# Sensor_Cameralink.net
KiCad netlist of a schematic drawn in EAGLE
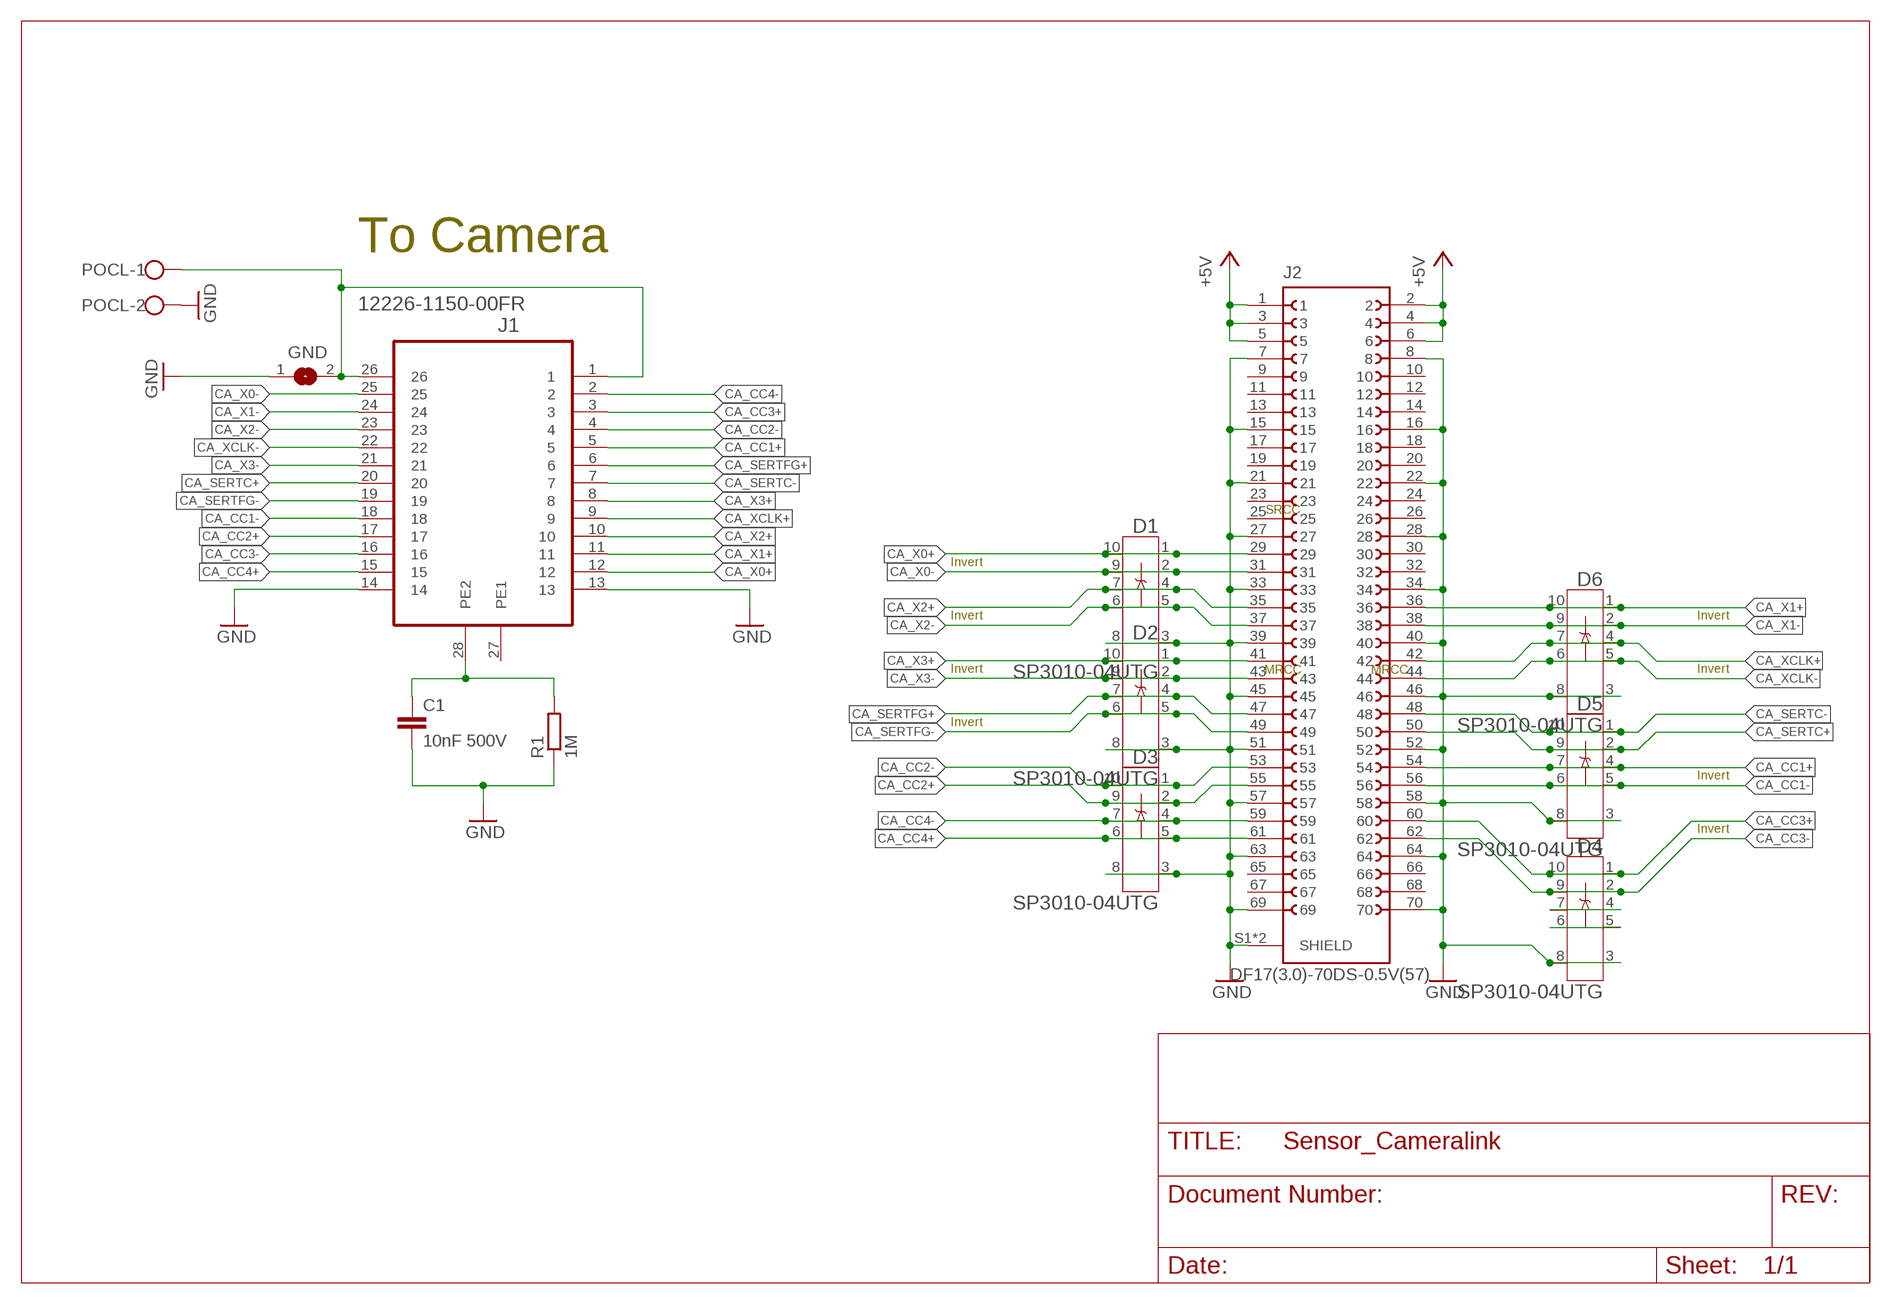
[diagram p0: schematic, sheet 1]

(export (version "E")
  (design (tool "Eeschema 10.0.6"))
  (components
    (comp (ref "C1")
      (value "10nF 500V")
      (footprint "eagle-import:C0805")
      (libsource (lib "eagle-import") (part "C-EUC0805"))
    )
    (comp (ref "D1")
      (value "SP3010-04UTG")
      (footprint "eagle-import:UDFEN-10_MO229_LTF")
      (libsource (lib "eagle-import") (part "SP3010-04UTG"))
    )
    (comp (ref "D2")
      (value "SP3010-04UTG")
      (footprint "eagle-import:UDFEN-10_MO229_LTF")
      (libsource (lib "eagle-import") (part "SP3010-04UTG"))
    )
    (comp (ref "D3")
      (value "SP3010-04UTG")
      (footprint "eagle-import:UDFEN-10_MO229_LTF")
      (libsource (lib "eagle-import") (part "SP3010-04UTG"))
    )
    (comp (ref "D4")
      (value "SP3010-04UTG")
      (footprint "eagle-import:UDFEN-10_MO229_LTF")
      (libsource (lib "eagle-import") (part "SP3010-04UTG"))
    )
    (comp (ref "D5")
      (value "SP3010-04UTG")
      (footprint "eagle-import:UDFEN-10_MO229_LTF")
      (libsource (lib "eagle-import") (part "SP3010-04UTG"))
    )
    (comp (ref "D6")
      (value "SP3010-04UTG")
      (footprint "eagle-import:UDFEN-10_MO229_LTF")
      (libsource (lib "eagle-import") (part "SP3010-04UTG"))
    )
    (comp (ref "GND") (value "SJ") (footprint "eagle-import:SJ") (libsource (lib "eagle-import") (part "SJ")))
    (comp (ref "J1")
      (value "12226-1150-00FR")
      (footprint "eagle-import:3M_12226-1150-00FR")
      (libsource (lib "eagle-import") (part "12226-1150-00FR"))
    )
    (comp (ref "J2")
      (value "DF17(3.0)-70DS-0.5V(57)")
      (footprint "eagle-import:DF17(3.0)-70DS-0.5V(57)")
      (libsource (lib "eagle-import") (part "DF17(3.0)-70DS-0.5V(57)"))
    )
    (comp (ref "POCL")
      (value "W237-102")
      (footprint "eagle-import:W237-102")
      (fields (field (name "MPN") "237-102"))
      (libsource (lib "eagle-import") (part "W237-102"))
    )
    (comp (ref "R1")
      (value "1M")
      (footprint "eagle-import:R0805")
      (libsource (lib "eagle-import") (part "R-EU_R0805"))
    )
  )
  (nets
    (net (code "1") (name "+5V") (class "Default")
      (node (ref "J2") (pin "1") (pinfunction "1_1") (pintype "passive"))
      (node (ref "J2") (pin "2") (pinfunction "2_2") (pintype "passive"))
      (node (ref "J2") (pin "3") (pinfunction "3_3") (pintype "passive"))
      (node (ref "J2") (pin "4") (pinfunction "4_4") (pintype "passive"))
      (node (ref "J2") (pin "5") (pinfunction "5_5") (pintype "passive"))
      (node (ref "J2") (pin "6") (pinfunction "6_6") (pintype "passive"))
    )
    (net (code "2") (name "CA_CC1+") (class "Default")
      (node (ref "D5") (pin "4") (pinfunction "4_4") (pintype "passive"))
      (node (ref "D5") (pin "7") (pinfunction "7_7") (pintype "passive"))
      (node (ref "J1") (pin "5") (pinfunction "5_5") (pintype "passive"))
      (node (ref "J2") (pin "54") (pinfunction "54_54") (pintype "passive"))
    )
    (net (code "3") (name "CA_CC1-") (class "Default")
      (node (ref "D5") (pin "5") (pinfunction "5_5") (pintype "passive"))
      (node (ref "D5") (pin "6") (pinfunction "6_6") (pintype "passive"))
      (node (ref "J1") (pin "18") (pinfunction "18_18") (pintype "passive"))
      (node (ref "J2") (pin "56") (pinfunction "56_56") (pintype "passive"))
    )
    (net (code "4") (name "CA_CC2+") (class "Default")
      (node (ref "D3") (pin "2") (pinfunction "2_2") (pintype "passive"))
      (node (ref "D3") (pin "9") (pinfunction "9_9") (pintype "passive"))
      (node (ref "J1") (pin "17") (pinfunction "17_17") (pintype "passive"))
      (node (ref "J2") (pin "55") (pinfunction "55_55") (pintype "passive"))
    )
    (net (code "5") (name "CA_CC2-") (class "Default")
      (node (ref "D3") (pin "1") (pinfunction "1_1") (pintype "passive"))
      (node (ref "D3") (pin "10") (pinfunction "10_10") (pintype "passive"))
      (node (ref "J1") (pin "4") (pinfunction "4_4") (pintype "passive"))
      (node (ref "J2") (pin "53") (pinfunction "53_53") (pintype "passive"))
    )
    (net (code "6") (name "CA_CC3+") (class "Default")
      (node (ref "D4") (pin "1") (pinfunction "1_1") (pintype "passive"))
      (node (ref "D4") (pin "10") (pinfunction "10_10") (pintype "passive"))
      (node (ref "J1") (pin "3") (pinfunction "3_3") (pintype "passive"))
      (node (ref "J2") (pin "60") (pinfunction "60_60") (pintype "passive"))
    )
    (net (code "7") (name "CA_CC3-") (class "Default")
      (node (ref "D4") (pin "2") (pinfunction "2_2") (pintype "passive"))
      (node (ref "D4") (pin "9") (pinfunction "9_9") (pintype "passive"))
      (node (ref "J1") (pin "16") (pinfunction "16_16") (pintype "passive"))
      (node (ref "J2") (pin "62") (pinfunction "62_62") (pintype "passive"))
    )
    (net (code "8") (name "CA_CC4+") (class "Default")
      (node (ref "D3") (pin "5") (pinfunction "5_5") (pintype "passive"))
      (node (ref "D3") (pin "6") (pinfunction "6_6") (pintype "passive"))
      (node (ref "J1") (pin "15") (pinfunction "15_15") (pintype "passive"))
      (node (ref "J2") (pin "61") (pinfunction "61_61") (pintype "passive"))
    )
    (net (code "9") (name "CA_CC4-") (class "Default")
      (node (ref "D3") (pin "4") (pinfunction "4_4") (pintype "passive"))
      (node (ref "D3") (pin "7") (pinfunction "7_7") (pintype "passive"))
      (node (ref "J1") (pin "2") (pinfunction "2_2") (pintype "passive"))
      (node (ref "J2") (pin "59") (pinfunction "59_59") (pintype "passive"))
    )
    (net (code "10") (name "CA_SERTC+") (class "Default")
      (node (ref "D5") (pin "2") (pinfunction "2_2") (pintype "passive"))
      (node (ref "D5") (pin "9") (pinfunction "9_9") (pintype "passive"))
      (node (ref "J1") (pin "20") (pinfunction "20_20") (pintype "passive"))
      (node (ref "J2") (pin "50") (pinfunction "50_50") (pintype "passive"))
    )
    (net (code "11") (name "CA_SERTC-") (class "Default")
      (node (ref "D5") (pin "1") (pinfunction "1_1") (pintype "passive"))
      (node (ref "D5") (pin "10") (pinfunction "10_10") (pintype "passive"))
      (node (ref "J1") (pin "7") (pinfunction "7_7") (pintype "passive"))
      (node (ref "J2") (pin "48") (pinfunction "48_48") (pintype "passive"))
    )
    (net (code "12") (name "CA_SERTFG+") (class "Default")
      (node (ref "D2") (pin "4") (pinfunction "4_4") (pintype "passive"))
      (node (ref "D2") (pin "7") (pinfunction "7_7") (pintype "passive"))
      (node (ref "J1") (pin "6") (pinfunction "6_6") (pintype "passive"))
      (node (ref "J2") (pin "47") (pinfunction "47_47") (pintype "passive"))
    )
    (net (code "13") (name "CA_SERTFG-") (class "Default")
      (node (ref "D2") (pin "5") (pinfunction "5_5") (pintype "passive"))
      (node (ref "D2") (pin "6") (pinfunction "6_6") (pintype "passive"))
      (node (ref "J1") (pin "19") (pinfunction "19_19") (pintype "passive"))
      (node (ref "J2") (pin "49") (pinfunction "49_49") (pintype "passive"))
    )
    (net (code "14") (name "CA_X0+") (class "Default")
      (node (ref "D1") (pin "1") (pinfunction "1_1") (pintype "passive"))
      (node (ref "D1") (pin "10") (pinfunction "10_10") (pintype "passive"))
      (node (ref "J1") (pin "12") (pinfunction "12_12") (pintype "passive"))
      (node (ref "J2") (pin "29") (pinfunction "29_29") (pintype "passive"))
    )
    (net (code "15") (name "CA_X0-") (class "Default")
      (node (ref "D1") (pin "2") (pinfunction "2_2") (pintype "passive"))
      (node (ref "D1") (pin "9") (pinfunction "9_9") (pintype "passive"))
      (node (ref "J1") (pin "25") (pinfunction "25_25") (pintype "passive"))
      (node (ref "J2") (pin "31") (pinfunction "31_31") (pintype "passive"))
    )
    (net (code "16") (name "CA_X1+") (class "Default")
      (node (ref "D6") (pin "1") (pinfunction "1_1") (pintype "passive"))
      (node (ref "D6") (pin "10") (pinfunction "10_10") (pintype "passive"))
      (node (ref "J1") (pin "11") (pinfunction "11_11") (pintype "passive"))
      (node (ref "J2") (pin "36") (pinfunction "36_36") (pintype "passive"))
    )
    (net (code "17") (name "CA_X1-") (class "Default")
      (node (ref "D6") (pin "2") (pinfunction "2_2") (pintype "passive"))
      (node (ref "D6") (pin "9") (pinfunction "9_9") (pintype "passive"))
      (node (ref "J1") (pin "24") (pinfunction "24_24") (pintype "passive"))
      (node (ref "J2") (pin "38") (pinfunction "38_38") (pintype "passive"))
    )
    (net (code "18") (name "CA_X2+") (class "Default")
      (node (ref "D1") (pin "4") (pinfunction "4_4") (pintype "passive"))
      (node (ref "D1") (pin "7") (pinfunction "7_7") (pintype "passive"))
      (node (ref "J1") (pin "10") (pinfunction "10_10") (pintype "passive"))
      (node (ref "J2") (pin "35") (pinfunction "35_35") (pintype "passive"))
    )
    (net (code "19") (name "CA_X2-") (class "Default")
      (node (ref "D1") (pin "5") (pinfunction "5_5") (pintype "passive"))
      (node (ref "D1") (pin "6") (pinfunction "6_6") (pintype "passive"))
      (node (ref "J1") (pin "23") (pinfunction "23_23") (pintype "passive"))
      (node (ref "J2") (pin "37") (pinfunction "37_37") (pintype "passive"))
    )
    (net (code "20") (name "CA_X3+") (class "Default")
      (node (ref "D2") (pin "1") (pinfunction "1_1") (pintype "passive"))
      (node (ref "D2") (pin "10") (pinfunction "10_10") (pintype "passive"))
      (node (ref "J1") (pin "8") (pinfunction "8_8") (pintype "passive"))
      (node (ref "J2") (pin "41") (pinfunction "41_41") (pintype "passive"))
    )
    (net (code "21") (name "CA_X3-") (class "Default")
      (node (ref "D2") (pin "2") (pinfunction "2_2") (pintype "passive"))
      (node (ref "D2") (pin "9") (pinfunction "9_9") (pintype "passive"))
      (node (ref "J1") (pin "21") (pinfunction "21_21") (pintype "passive"))
      (node (ref "J2") (pin "43") (pinfunction "43_43") (pintype "passive"))
    )
    (net (code "22") (name "CA_XCLK+") (class "Default")
      (node (ref "D6") (pin "4") (pinfunction "4_4") (pintype "passive"))
      (node (ref "D6") (pin "7") (pinfunction "7_7") (pintype "passive"))
      (node (ref "J1") (pin "9") (pinfunction "9_9") (pintype "passive"))
      (node (ref "J2") (pin "42") (pinfunction "42_42") (pintype "passive"))
    )
    (net (code "23") (name "CA_XCLK-") (class "Default")
      (node (ref "D6") (pin "5") (pinfunction "5_5") (pintype "passive"))
      (node (ref "D6") (pin "6") (pinfunction "6_6") (pintype "passive"))
      (node (ref "J1") (pin "22") (pinfunction "22_22") (pintype "passive"))
      (node (ref "J2") (pin "44") (pinfunction "44_44") (pintype "passive"))
    )
    (net (code "24") (name "GND") (class "Default")
      (node (ref "C1") (pin "2") (pinfunction "2_2") (pintype "passive"))
      (node (ref "D1") (pin "3") (pinfunction "3_3") (pintype "passive"))
      (node (ref "D1") (pin "8") (pinfunction "8_8") (pintype "passive"))
      (node (ref "D2") (pin "3") (pinfunction "3_3") (pintype "passive"))
      (node (ref "D2") (pin "8") (pinfunction "8_8") (pintype "passive"))
      (node (ref "D3") (pin "3") (pinfunction "3_3") (pintype "passive"))
      (node (ref "D3") (pin "8") (pinfunction "8_8") (pintype "passive"))
      (node (ref "D4") (pin "3") (pinfunction "3_3") (pintype "passive"))
      (node (ref "D4") (pin "8") (pinfunction "8_8") (pintype "passive"))
      (node (ref "D5") (pin "3") (pinfunction "3_3") (pintype "passive"))
      (node (ref "D5") (pin "8") (pinfunction "8_8") (pintype "passive"))
      (node (ref "D6") (pin "3") (pinfunction "3_3") (pintype "passive"))
      (node (ref "D6") (pin "8") (pinfunction "8_8") (pintype "passive"))
      (node (ref "GND") (pin "1") (pinfunction "1_1") (pintype "passive"))
      (node (ref "J1") (pin "13") (pinfunction "13_13") (pintype "passive"))
      (node (ref "J1") (pin "14") (pinfunction "14_14") (pintype "passive"))
      (node (ref "J2") (pin "15") (pinfunction "15_15") (pintype "passive"))
      (node (ref "J2") (pin "16") (pinfunction "16_16") (pintype "passive"))
      (node (ref "J2") (pin "21") (pinfunction "21_21") (pintype "passive"))
      (node (ref "J2") (pin "22") (pinfunction "22_22") (pintype "passive"))
      (node (ref "J2") (pin "27") (pinfunction "27_27") (pintype "passive"))
      (node (ref "J2") (pin "28") (pinfunction "28_28") (pintype "passive"))
      (node (ref "J2") (pin "33") (pinfunction "33_33") (pintype "passive"))
      (node (ref "J2") (pin "34") (pinfunction "34_34") (pintype "passive"))
      (node (ref "J2") (pin "39") (pinfunction "39_39") (pintype "passive"))
      (node (ref "J2") (pin "40") (pinfunction "40_40") (pintype "passive"))
      (node (ref "J2") (pin "45") (pinfunction "45_45") (pintype "passive"))
      (node (ref "J2") (pin "46") (pinfunction "46_46") (pintype "passive"))
      (node (ref "J2") (pin "51") (pinfunction "51_51") (pintype "passive"))
      (node (ref "J2") (pin "52") (pinfunction "52_52") (pintype "passive"))
      (node (ref "J2") (pin "57") (pinfunction "57_57") (pintype "passive"))
      (node (ref "J2") (pin "58") (pinfunction "58_58") (pintype "passive"))
      (node (ref "J2") (pin "63") (pinfunction "63_63") (pintype "passive"))
      (node (ref "J2") (pin "64") (pinfunction "64_64") (pintype "passive"))
      (node (ref "J2") (pin "69") (pinfunction "69_69") (pintype "passive"))
      (node (ref "J2") (pin "7") (pinfunction "7_7") (pintype "passive"))
      (node (ref "J2") (pin "70") (pinfunction "70_70") (pintype "passive"))
      (node (ref "J2") (pin "8") (pinfunction "8_8") (pintype "passive"))
      (node (ref "J2") (pin "S1") (pinfunction "SHIELD_S1") (pintype "passive"))
      (node (ref "J2") (pin "S2") (pinfunction "SHIELD_S2") (pintype "passive"))
      (node (ref "POCL") (pin "2") (pinfunction "KL_2") (pintype "passive"))
      (node (ref "R1") (pin "1") (pinfunction "1_1") (pintype "passive"))
    )
    (net (code "25") (name "Net-(D4-Pad4)") (class "Default")
      (node (ref "D4") (pin "4") (pinfunction "4_4") (pintype "passive"))
      (node (ref "D4") (pin "7") (pinfunction "7_7") (pintype "passive"))
    )
    (net (code "26") (name "Net-(D4-Pad5)") (class "Default")
      (node (ref "D4") (pin "5") (pinfunction "5_5") (pintype "passive"))
      (node (ref "D4") (pin "6") (pinfunction "6_6") (pintype "passive"))
    )
    (net (code "27") (name "Net-(J1-PE2)") (class "Default")
      (node (ref "C1") (pin "1") (pinfunction "1_1") (pintype "passive"))
      (node (ref "J1") (pin "28") (pinfunction "PE2_28") (pintype "bidirectional"))
      (node (ref "R1") (pin "2") (pinfunction "2_2") (pintype "passive"))
    )
    (net (code "28") (name "Net-(POCLA-KL)") (class "Default")
      (node (ref "GND") (pin "2") (pinfunction "2_2") (pintype "passive"))
      (node (ref "J1") (pin "1") (pinfunction "1_1") (pintype "passive"))
      (node (ref "J1") (pin "26") (pinfunction "26_26") (pintype "passive"))
      (node (ref "POCL") (pin "1") (pinfunction "KL_1") (pintype "passive"))
    )
    (net (code "29") (name "unconnected-(J1-PE1-Pad27)") (class "Default")
      (node (ref "J1") (pin "27") (pinfunction "PE1_27") (pintype "bidirectional"))
    )
    (net (code "30") (name "unconnected-(J2-Pad9)") (class "Default")
      (node (ref "J2") (pin "9") (pinfunction "9_9") (pintype "passive"))
    )
    (net (code "31") (name "unconnected-(J2-Pad10)") (class "Default")
      (node (ref "J2") (pin "10") (pinfunction "10_10") (pintype "passive"))
    )
    (net (code "32") (name "unconnected-(J2-Pad11)") (class "Default")
      (node (ref "J2") (pin "11") (pinfunction "11_11") (pintype "passive"))
    )
    (net (code "33") (name "unconnected-(J2-Pad12)") (class "Default")
      (node (ref "J2") (pin "12") (pinfunction "12_12") (pintype "passive"))
    )
    (net (code "34") (name "unconnected-(J2-Pad13)") (class "Default")
      (node (ref "J2") (pin "13") (pinfunction "13_13") (pintype "passive"))
    )
    (net (code "35") (name "unconnected-(J2-Pad14)") (class "Default")
      (node (ref "J2") (pin "14") (pinfunction "14_14") (pintype "passive"))
    )
    (net (code "36") (name "unconnected-(J2-Pad17)") (class "Default")
      (node (ref "J2") (pin "17") (pinfunction "17_17") (pintype "passive"))
    )
    (net (code "37") (name "unconnected-(J2-Pad18)") (class "Default")
      (node (ref "J2") (pin "18") (pinfunction "18_18") (pintype "passive"))
    )
    (net (code "38") (name "unconnected-(J2-Pad19)") (class "Default")
      (node (ref "J2") (pin "19") (pinfunction "19_19") (pintype "passive"))
    )
    (net (code "39") (name "unconnected-(J2-Pad20)") (class "Default")
      (node (ref "J2") (pin "20") (pinfunction "20_20") (pintype "passive"))
    )
    (net (code "40") (name "unconnected-(J2-Pad23)") (class "Default")
      (node (ref "J2") (pin "23") (pinfunction "23_23") (pintype "passive"))
    )
    (net (code "41") (name "unconnected-(J2-Pad24)") (class "Default")
      (node (ref "J2") (pin "24") (pinfunction "24_24") (pintype "passive"))
    )
    (net (code "42") (name "unconnected-(J2-Pad25)") (class "Default")
      (node (ref "J2") (pin "25") (pinfunction "25_25") (pintype "passive"))
    )
    (net (code "43") (name "unconnected-(J2-Pad26)") (class "Default")
      (node (ref "J2") (pin "26") (pinfunction "26_26") (pintype "passive"))
    )
    (net (code "44") (name "unconnected-(J2-Pad30)") (class "Default")
      (node (ref "J2") (pin "30") (pinfunction "30_30") (pintype "passive"))
    )
    (net (code "45") (name "unconnected-(J2-Pad32)") (class "Default")
      (node (ref "J2") (pin "32") (pinfunction "32_32") (pintype "passive"))
    )
    (net (code "46") (name "unconnected-(J2-Pad65)") (class "Default")
      (node (ref "J2") (pin "65") (pinfunction "65_65") (pintype "passive"))
    )
    (net (code "47") (name "unconnected-(J2-Pad66)") (class "Default")
      (node (ref "J2") (pin "66") (pinfunction "66_66") (pintype "passive"))
    )
    (net (code "48") (name "unconnected-(J2-Pad67)") (class "Default")
      (node (ref "J2") (pin "67") (pinfunction "67_67") (pintype "passive"))
    )
    (net (code "49") (name "unconnected-(J2-Pad68)") (class "Default")
      (node (ref "J2") (pin "68") (pinfunction "68_68") (pintype "passive"))
    )
  )
)
